# Current_AC.net
KiCad netlist of a schematic drawn in Altium Designer
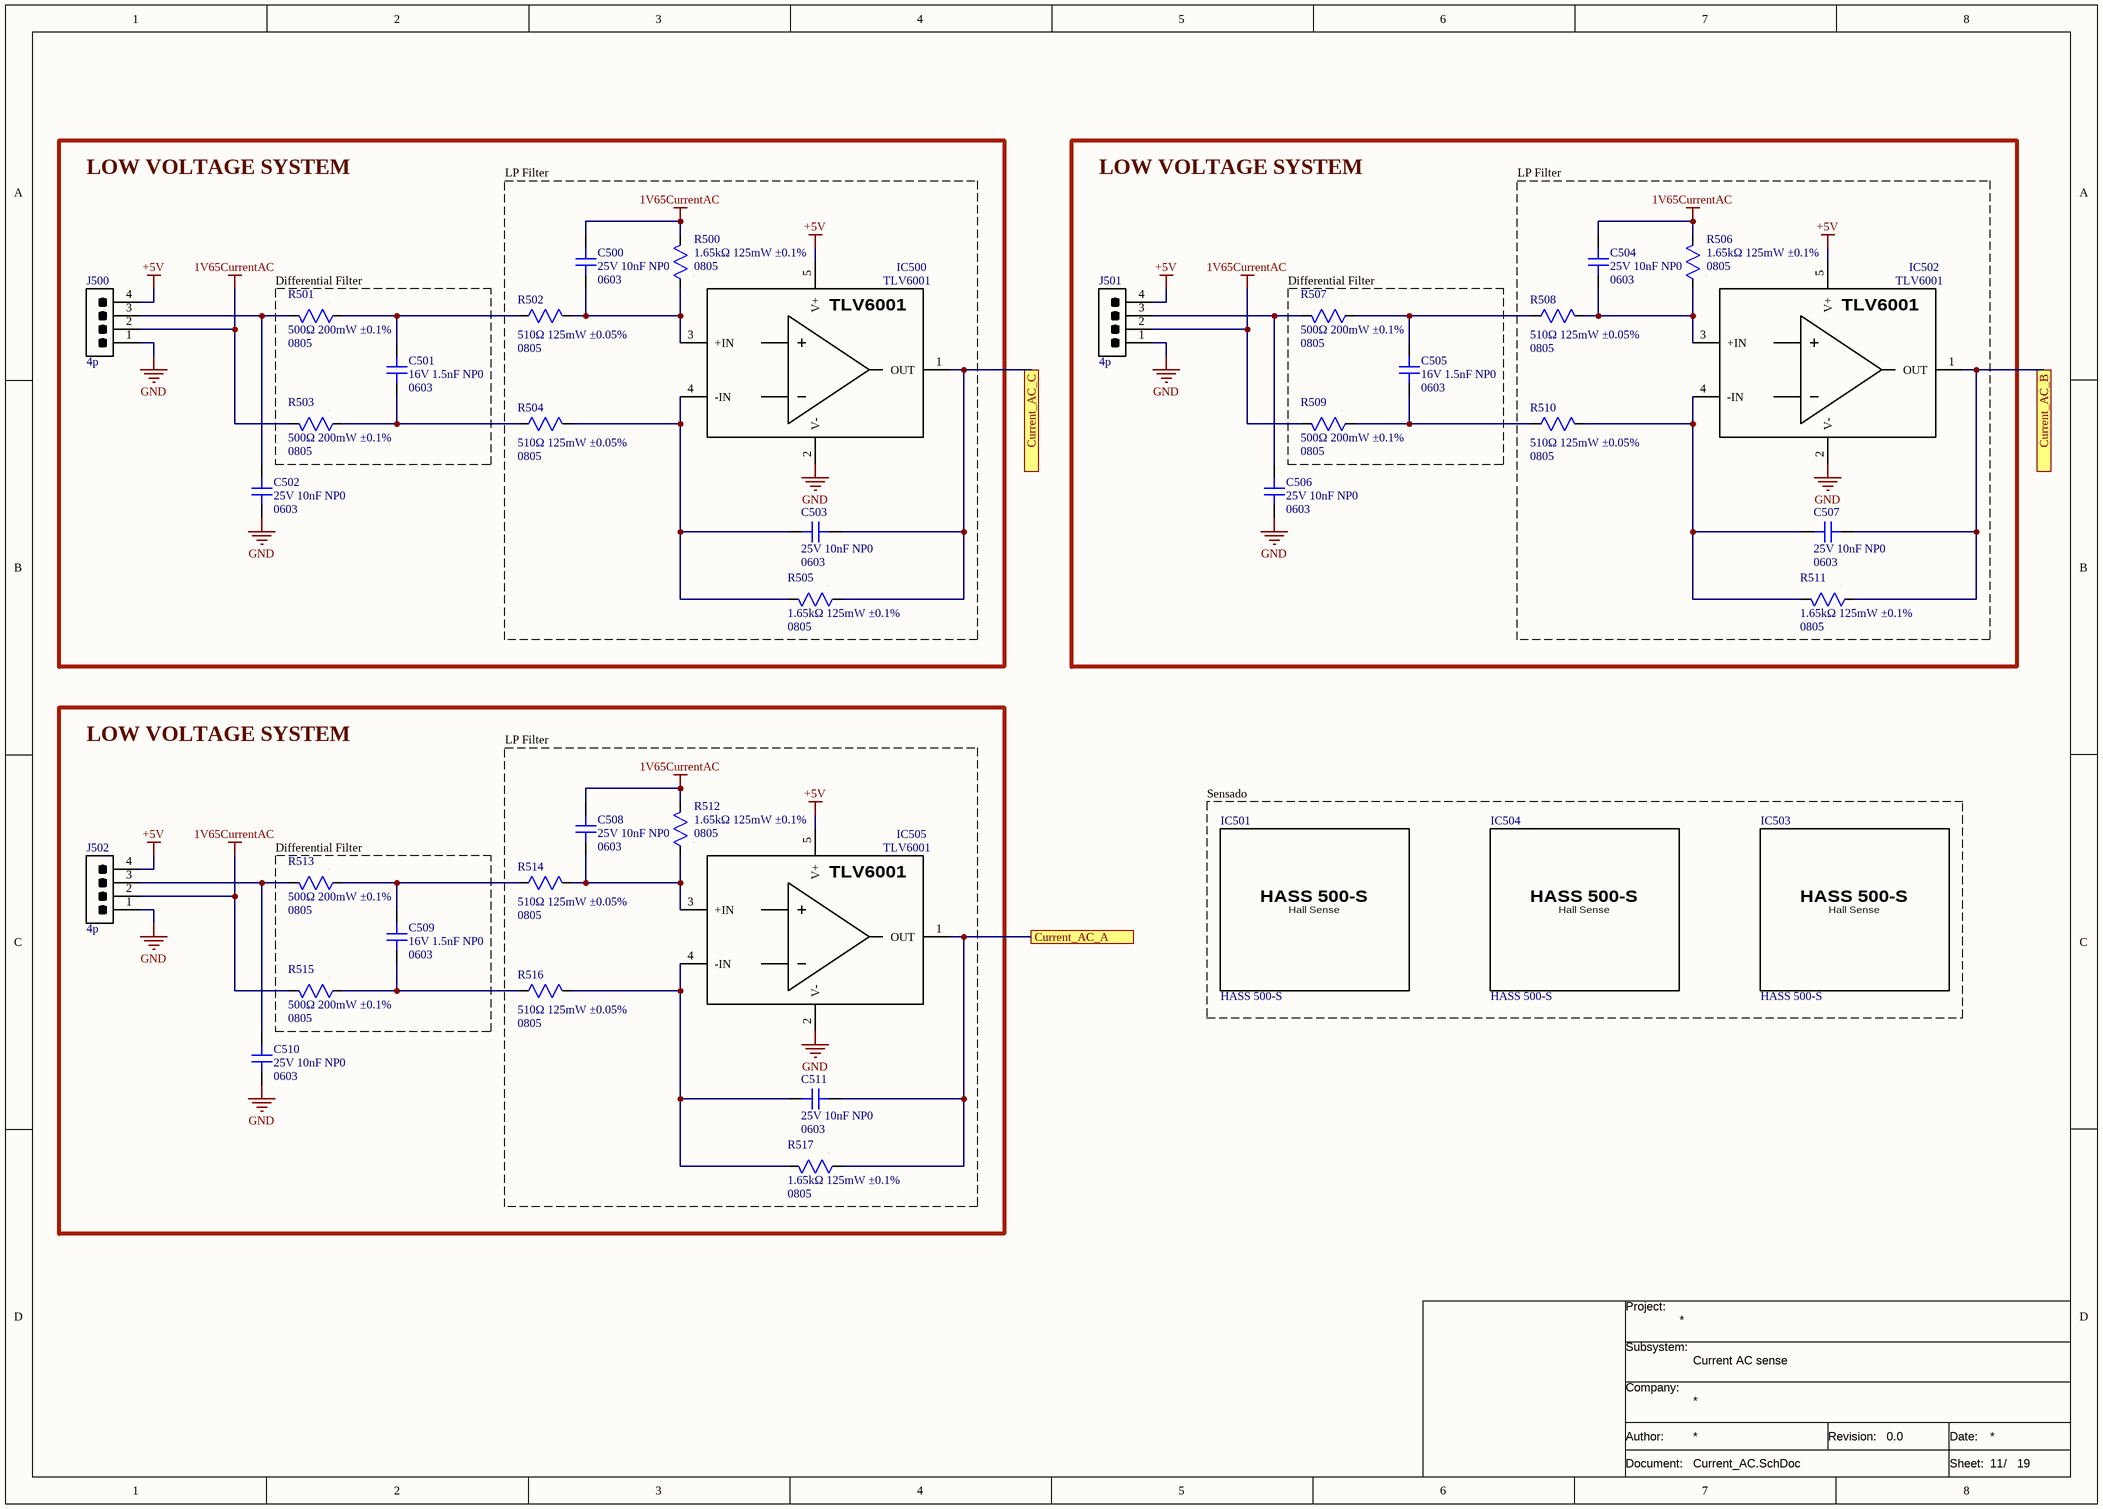
[diagram p0: Current_AC.SchDoc]

(export (version "E")
  (design (tool "Eeschema 10.0.6"))
  (components
    (comp (ref "C500")
      (value "25V 10nF NP0")
      (footprint "CAP SMD 0603")
      (description "Condensadores de cerámica multicapa (MLCC- SMD/SMT) 0.01 uF 25 VDC 1% 0603 C0G (NP0) AEC-Q200")
      (fields
        (field (name "PACKAGE") "0603")
        (field (name "MPN") "GRT1885C1E103FA02D")
        (field (name "MANUFACTURER") "muRata")
      )
      (libsource (lib "eUSR_Database") (part "CAP non polarized"))
    )
    (comp (ref "C501")
      (value "16V 1.5nF NP0")
      (footprint "CAP SMD 0603")
      (description "Condensadores de cerámica multicapa (MLCC- SMD/SMT) 25V 1500pF C0G 0603 1%")
      (fields
        (field (name "PACKAGE") "0603")
        (field (name "MPN") "C0603C152F3GECTU")
        (field (name "MANUFACTURER") "KEMET")
      )
      (libsource (lib "eUSR_Database") (part "CAP non polarized"))
    )
    (comp (ref "C502")
      (value "25V 10nF NP0")
      (footprint "CAP SMD 0603")
      (description "Condensadores de cerámica multicapa (MLCC- SMD/SMT) 0.01 uF 25 VDC 1% 0603 C0G (NP0) AEC-Q200")
      (fields
        (field (name "PACKAGE") "0603")
        (field (name "MPN") "GRT1885C1E103FA02D")
        (field (name "MANUFACTURER") "muRata")
      )
      (libsource (lib "eUSR_Database") (part "CAP non polarized"))
    )
    (comp (ref "C503")
      (value "25V 10nF NP0")
      (footprint "CAP SMD 0603")
      (description "Condensadores de cerámica multicapa (MLCC- SMD/SMT) 0.01 uF 25 VDC 1% 0603 C0G (NP0) AEC-Q200")
      (fields
        (field (name "PACKAGE") "0603")
        (field (name "MPN") "GRT1885C1E103FA02D")
        (field (name "MANUFACTURER") "muRata")
      )
      (libsource (lib "eUSR_Database") (part "CAP non polarized"))
    )
    (comp (ref "C504")
      (value "25V 10nF NP0")
      (footprint "CAP SMD 0603")
      (description "Condensadores de cerámica multicapa (MLCC- SMD/SMT) 0.01 uF 25 VDC 1% 0603 C0G (NP0) AEC-Q200")
      (fields
        (field (name "PACKAGE") "0603")
        (field (name "MPN") "GRT1885C1E103FA02D")
        (field (name "MANUFACTURER") "muRata")
      )
      (libsource (lib "eUSR_Database") (part "CAP non polarized"))
    )
    (comp (ref "C505")
      (value "16V 1.5nF NP0")
      (footprint "CAP SMD 0603")
      (description "Condensadores de cerámica multicapa (MLCC- SMD/SMT) 25V 1500pF C0G 0603 1%")
      (fields
        (field (name "PACKAGE") "0603")
        (field (name "MPN") "C0603C152F3GECTU")
        (field (name "MANUFACTURER") "KEMET")
      )
      (libsource (lib "eUSR_Database") (part "CAP non polarized"))
    )
    (comp (ref "C506")
      (value "25V 10nF NP0")
      (footprint "CAP SMD 0603")
      (description "Condensadores de cerámica multicapa (MLCC- SMD/SMT) 0.01 uF 25 VDC 1% 0603 C0G (NP0) AEC-Q200")
      (fields
        (field (name "PACKAGE") "0603")
        (field (name "MPN") "GRT1885C1E103FA02D")
        (field (name "MANUFACTURER") "muRata")
      )
      (libsource (lib "eUSR_Database") (part "CAP non polarized"))
    )
    (comp (ref "C507")
      (value "25V 10nF NP0")
      (footprint "CAP SMD 0603")
      (description "Condensadores de cerámica multicapa (MLCC- SMD/SMT) 0.01 uF 25 VDC 1% 0603 C0G (NP0) AEC-Q200")
      (fields
        (field (name "PACKAGE") "0603")
        (field (name "MPN") "GRT1885C1E103FA02D")
        (field (name "MANUFACTURER") "muRata")
      )
      (libsource (lib "eUSR_Database") (part "CAP non polarized"))
    )
    (comp (ref "C508")
      (value "25V 10nF NP0")
      (footprint "CAP SMD 0603")
      (description "Condensadores de cerámica multicapa (MLCC- SMD/SMT) 0.01 uF 25 VDC 1% 0603 C0G (NP0) AEC-Q200")
      (fields
        (field (name "PACKAGE") "0603")
        (field (name "MPN") "GRT1885C1E103FA02D")
        (field (name "MANUFACTURER") "muRata")
      )
      (libsource (lib "eUSR_Database") (part "CAP non polarized"))
    )
    (comp (ref "C509")
      (value "16V 1.5nF NP0")
      (footprint "CAP SMD 0603")
      (description "Condensadores de cerámica multicapa (MLCC- SMD/SMT) 25V 1500pF C0G 0603 1%")
      (fields
        (field (name "PACKAGE") "0603")
        (field (name "MPN") "C0603C152F3GECTU")
        (field (name "MANUFACTURER") "KEMET")
      )
      (libsource (lib "eUSR_Database") (part "CAP non polarized"))
    )
    (comp (ref "C510")
      (value "25V 10nF NP0")
      (footprint "CAP SMD 0603")
      (description "Condensadores de cerámica multicapa (MLCC- SMD/SMT) 0.01 uF 25 VDC 1% 0603 C0G (NP0) AEC-Q200")
      (fields
        (field (name "PACKAGE") "0603")
        (field (name "MPN") "GRT1885C1E103FA02D")
        (field (name "MANUFACTURER") "muRata")
      )
      (libsource (lib "eUSR_Database") (part "CAP non polarized"))
    )
    (comp (ref "C511")
      (value "25V 10nF NP0")
      (footprint "CAP SMD 0603")
      (description "Condensadores de cerámica multicapa (MLCC- SMD/SMT) 0.01 uF 25 VDC 1% 0603 C0G (NP0) AEC-Q200")
      (fields
        (field (name "PACKAGE") "0603")
        (field (name "MPN") "GRT1885C1E103FA02D")
        (field (name "MANUFACTURER") "muRata")
      )
      (libsource (lib "eUSR_Database") (part "CAP non polarized"))
    )
    (comp (ref "IC500")
      (value "TLV6001")
      (footprint "SOT-23-5")
      (fields (field (name "MPN") "TLV6001UIDBVR") (field (name "MANUFACTURER") "Texas Instruments"))
      (libsource (lib "eUSR_Database") (part "TLV6001"))
    )
    (comp (ref "IC501")
      (value "HASS 500-S")
      (footprint "HASS 500-S")
      (description "Sensores de corriente montados en placa")
      (fields (field (name "MANUFACTURER") "LEM"))
      (libsource (lib "eUSR_Database") (part "HASS 500-S"))
    )
    (comp (ref "IC502")
      (value "TLV6001")
      (footprint "SOT-23-5")
      (fields (field (name "MPN") "TLV6001UIDBVR") (field (name "MANUFACTURER") "Texas Instruments"))
      (libsource (lib "eUSR_Database") (part "TLV6001"))
    )
    (comp (ref "IC503")
      (value "HASS 500-S")
      (footprint "HASS 500-S")
      (description "Sensores de corriente montados en placa")
      (fields (field (name "MANUFACTURER") "LEM"))
      (libsource (lib "eUSR_Database") (part "HASS 500-S"))
    )
    (comp (ref "IC504")
      (value "HASS 500-S")
      (footprint "HASS 500-S")
      (description "Sensores de corriente montados en placa")
      (fields (field (name "MANUFACTURER") "LEM"))
      (libsource (lib "eUSR_Database") (part "HASS 500-S"))
    )
    (comp (ref "IC505")
      (value "TLV6001")
      (footprint "SOT-23-5")
      (fields (field (name "MPN") "TLV6001UIDBVR") (field (name "MANUFACTURER") "Texas Instruments"))
      (libsource (lib "eUSR_Database") (part "TLV6001"))
    )
    (comp (ref "J500")
      (value "4p")
      (footprint "B4B-XH-A-BK(LF)(SN)")
      (description "Alojamientos de cables y cabecera XH HEADER (TOP)")
      (fields (field (name "MPN") "B4B-XH-A-BK(LF)(SN)") (field (name "MANUFACTURER") "JST"))
      (libsource (lib "eUSR_Database") (part "CONN 4P"))
    )
    (comp (ref "J501")
      (value "4p")
      (footprint "B4B-XH-A-BK(LF)(SN)")
      (description "Alojamientos de cables y cabecera XH HEADER (TOP)")
      (fields (field (name "MPN") "B4B-XH-A-BK(LF)(SN)") (field (name "MANUFACTURER") "JST"))
      (libsource (lib "eUSR_Database") (part "CONN 4P"))
    )
    (comp (ref "J502")
      (value "4p")
      (footprint "B4B-XH-A-BK(LF)(SN)")
      (description "Alojamientos de cables y cabecera XH HEADER (TOP)")
      (fields (field (name "MPN") "B4B-XH-A-BK(LF)(SN)") (field (name "MANUFACTURER") "JST"))
      (libsource (lib "eUSR_Database") (part "CONN 4P"))
    )
    (comp (ref "R500")
      (value "1.65kΩ 125mW ±0.1%")
      (footprint "RES SMD 0805")
      (description "Thin Film Resistors MCU 0805-15 0.1% P1 1K65")
      (fields
        (field (name "PACKAGE") "0805")
        (field (name "MPN") "MCU08050E1651BP100")
        (field (name "MANUFACTURER") "Vishay")
      )
      (libsource (lib "eUSR_Database") (part "RES"))
    )
    (comp (ref "R501")
      (value "500Ω 200mW ±0.1%")
      (footprint "RES SMD 0805")
      (description "Resistores de película fina - SMD 0.2W 500ohm 0.1% 10ppm")
      (fields
        (field (name "PACKAGE") "0805")
        (field (name "MPN") "PTN0805Y5000BST1")
        (field (name "MANUFACTURER") "Vishay")
      )
      (libsource (lib "eUSR_Database") (part "RES"))
    )
    (comp (ref "R502")
      (value "510Ω 125mW ±0.05%")
      (footprint "RES SMD 0805")
      (description "Resistores de película fina - SMD 1/8W 510 Ohms 0.05% 0805 10ppm")
      (fields
        (field (name "PACKAGE") "0805")
        (field (name "MPN") "RG2012N-511-W-T1")
        (field (name "MANUFACTURER") "Susumu")
      )
      (libsource (lib "eUSR_Database") (part "RES"))
    )
    (comp (ref "R503")
      (value "500Ω 200mW ±0.1%")
      (footprint "RES SMD 0805")
      (description "Resistores de película fina - SMD 0.2W 500ohm 0.1% 10ppm")
      (fields
        (field (name "PACKAGE") "0805")
        (field (name "MPN") "PTN0805Y5000BST1")
        (field (name "MANUFACTURER") "Vishay")
      )
      (libsource (lib "eUSR_Database") (part "RES"))
    )
    (comp (ref "R504")
      (value "510Ω 125mW ±0.05%")
      (footprint "RES SMD 0805")
      (description "Resistores de película fina - SMD 1/8W 510 Ohms 0.05% 0805 10ppm")
      (fields
        (field (name "PACKAGE") "0805")
        (field (name "MPN") "RG2012N-511-W-T1")
        (field (name "MANUFACTURER") "Susumu")
      )
      (libsource (lib "eUSR_Database") (part "RES"))
    )
    (comp (ref "R505")
      (value "1.65kΩ 125mW ±0.1%")
      (footprint "RES SMD 0805")
      (description "Thin Film Resistors MCU 0805-15 0.1% P1 1K65")
      (fields
        (field (name "PACKAGE") "0805")
        (field (name "MPN") "MCU08050E1651BP100")
        (field (name "MANUFACTURER") "Vishay")
      )
      (libsource (lib "eUSR_Database") (part "RES"))
    )
    (comp (ref "R506")
      (value "1.65kΩ 125mW ±0.1%")
      (footprint "RES SMD 0805")
      (description "Thin Film Resistors MCU 0805-15 0.1% P1 1K65")
      (fields
        (field (name "PACKAGE") "0805")
        (field (name "MPN") "MCU08050E1651BP100")
        (field (name "MANUFACTURER") "Vishay")
      )
      (libsource (lib "eUSR_Database") (part "RES"))
    )
    (comp (ref "R507")
      (value "500Ω 200mW ±0.1%")
      (footprint "RES SMD 0805")
      (description "Resistores de película fina - SMD 0.2W 500ohm 0.1% 10ppm")
      (fields
        (field (name "PACKAGE") "0805")
        (field (name "MPN") "PTN0805Y5000BST1")
        (field (name "MANUFACTURER") "Vishay")
      )
      (libsource (lib "eUSR_Database") (part "RES"))
    )
    (comp (ref "R508")
      (value "510Ω 125mW ±0.05%")
      (footprint "RES SMD 0805")
      (description "Resistores de película fina - SMD 1/8W 510 Ohms 0.05% 0805 10ppm")
      (fields
        (field (name "PACKAGE") "0805")
        (field (name "MPN") "RG2012N-511-W-T1")
        (field (name "MANUFACTURER") "Susumu")
      )
      (libsource (lib "eUSR_Database") (part "RES"))
    )
    (comp (ref "R509")
      (value "500Ω 200mW ±0.1%")
      (footprint "RES SMD 0805")
      (description "Resistores de película fina - SMD 0.2W 500ohm 0.1% 10ppm")
      (fields
        (field (name "PACKAGE") "0805")
        (field (name "MPN") "PTN0805Y5000BST1")
        (field (name "MANUFACTURER") "Vishay")
      )
      (libsource (lib "eUSR_Database") (part "RES"))
    )
    (comp (ref "R510")
      (value "510Ω 125mW ±0.05%")
      (footprint "RES SMD 0805")
      (description "Resistores de película fina - SMD 1/8W 510 Ohms 0.05% 0805 10ppm")
      (fields
        (field (name "PACKAGE") "0805")
        (field (name "MPN") "RG2012N-511-W-T1")
        (field (name "MANUFACTURER") "Susumu")
      )
      (libsource (lib "eUSR_Database") (part "RES"))
    )
    (comp (ref "R511")
      (value "1.65kΩ 125mW ±0.1%")
      (footprint "RES SMD 0805")
      (description "Thin Film Resistors MCU 0805-15 0.1% P1 1K65")
      (fields
        (field (name "PACKAGE") "0805")
        (field (name "MPN") "MCU08050E1651BP100")
        (field (name "MANUFACTURER") "Vishay")
      )
      (libsource (lib "eUSR_Database") (part "RES"))
    )
    (comp (ref "R512")
      (value "1.65kΩ 125mW ±0.1%")
      (footprint "RES SMD 0805")
      (description "Thin Film Resistors MCU 0805-15 0.1% P1 1K65")
      (fields
        (field (name "PACKAGE") "0805")
        (field (name "MPN") "MCU08050E1651BP100")
        (field (name "MANUFACTURER") "Vishay")
      )
      (libsource (lib "eUSR_Database") (part "RES"))
    )
    (comp (ref "R513")
      (value "500Ω 200mW ±0.1%")
      (footprint "RES SMD 0805")
      (description "Resistores de película fina - SMD 0.2W 500ohm 0.1% 10ppm")
      (fields
        (field (name "PACKAGE") "0805")
        (field (name "MPN") "PTN0805Y5000BST1")
        (field (name "MANUFACTURER") "Vishay")
      )
      (libsource (lib "eUSR_Database") (part "RES"))
    )
    (comp (ref "R514")
      (value "510Ω 125mW ±0.05%")
      (footprint "RES SMD 0805")
      (description "Resistores de película fina - SMD 1/8W 510 Ohms 0.05% 0805 10ppm")
      (fields
        (field (name "PACKAGE") "0805")
        (field (name "MPN") "RG2012N-511-W-T1")
        (field (name "MANUFACTURER") "Susumu")
      )
      (libsource (lib "eUSR_Database") (part "RES"))
    )
    (comp (ref "R515")
      (value "500Ω 200mW ±0.1%")
      (footprint "RES SMD 0805")
      (description "Resistores de película fina - SMD 0.2W 500ohm 0.1% 10ppm")
      (fields
        (field (name "PACKAGE") "0805")
        (field (name "MPN") "PTN0805Y5000BST1")
        (field (name "MANUFACTURER") "Vishay")
      )
      (libsource (lib "eUSR_Database") (part "RES"))
    )
    (comp (ref "R516")
      (value "510Ω 125mW ±0.05%")
      (footprint "RES SMD 0805")
      (description "Resistores de película fina - SMD 1/8W 510 Ohms 0.05% 0805 10ppm")
      (fields
        (field (name "PACKAGE") "0805")
        (field (name "MPN") "RG2012N-511-W-T1")
        (field (name "MANUFACTURER") "Susumu")
      )
      (libsource (lib "eUSR_Database") (part "RES"))
    )
    (comp (ref "R517")
      (value "1.65kΩ 125mW ±0.1%")
      (footprint "RES SMD 0805")
      (description "Thin Film Resistors MCU 0805-15 0.1% P1 1K65")
      (fields
        (field (name "PACKAGE") "0805")
        (field (name "MPN") "MCU08050E1651BP100")
        (field (name "MANUFACTURER") "Vishay")
      )
      (libsource (lib "eUSR_Database") (part "RES"))
    )
  )
  (nets
    (net (code "1") (name "+5V") (class "Default")
      (node (ref "IC500") (pin "5") (pinfunction "V+_5") (pintype "passive"))
      (node (ref "IC502") (pin "5") (pinfunction "V+_5") (pintype "passive"))
      (node (ref "IC505") (pin "5") (pinfunction "V+_5") (pintype "passive"))
      (node (ref "J500") (pin "4") (pinfunction "4_4") (pintype "passive"))
      (node (ref "J501") (pin "4") (pinfunction "4_4") (pintype "passive"))
      (node (ref "J502") (pin "4") (pinfunction "4_4") (pintype "passive"))
    )
    (net (code "2") (name "/Current_AC_A") (class "Default")
      (node (ref "C511") (pin "2") (pinfunction "2_2") (pintype "passive"))
      (node (ref "IC505") (pin "1") (pinfunction "OUT_1") (pintype "passive"))
      (node (ref "R517") (pin "1") (pinfunction "1_1") (pintype "passive"))
    )
    (net (code "3") (name "/Current_AC_B") (class "Default")
      (node (ref "C507") (pin "2") (pinfunction "2_2") (pintype "passive"))
      (node (ref "IC502") (pin "1") (pinfunction "OUT_1") (pintype "passive"))
      (node (ref "R511") (pin "1") (pinfunction "1_1") (pintype "passive"))
    )
    (net (code "4") (name "/Current_AC_C") (class "Default")
      (node (ref "C503") (pin "2") (pinfunction "2_2") (pintype "passive"))
      (node (ref "IC500") (pin "1") (pinfunction "OUT_1") (pintype "passive"))
      (node (ref "R505") (pin "1") (pinfunction "1_1") (pintype "passive"))
    )
    (net (code "5") (name "1V65CurrentAC") (class "Default")
      (node (ref "C500") (pin "1") (pinfunction "1_1") (pintype "passive"))
      (node (ref "C504") (pin "1") (pinfunction "1_1") (pintype "passive"))
      (node (ref "C508") (pin "1") (pinfunction "1_1") (pintype "passive"))
      (node (ref "J500") (pin "2") (pinfunction "2_2") (pintype "passive"))
      (node (ref "J501") (pin "2") (pinfunction "2_2") (pintype "passive"))
      (node (ref "J502") (pin "2") (pinfunction "2_2") (pintype "passive"))
      (node (ref "R500") (pin "2") (pinfunction "2_2") (pintype "passive"))
      (node (ref "R503") (pin "2") (pinfunction "2_2") (pintype "passive"))
      (node (ref "R506") (pin "2") (pinfunction "2_2") (pintype "passive"))
      (node (ref "R509") (pin "2") (pinfunction "2_2") (pintype "passive"))
      (node (ref "R512") (pin "2") (pinfunction "2_2") (pintype "passive"))
      (node (ref "R515") (pin "2") (pinfunction "2_2") (pintype "passive"))
    )
    (net (code "6") (name "GND") (class "Default")
      (node (ref "C502") (pin "2") (pinfunction "2_2") (pintype "passive"))
      (node (ref "C506") (pin "2") (pinfunction "2_2") (pintype "passive"))
      (node (ref "C510") (pin "2") (pinfunction "2_2") (pintype "passive"))
      (node (ref "IC500") (pin "2") (pinfunction "V-_2") (pintype "passive"))
      (node (ref "IC502") (pin "2") (pinfunction "V-_2") (pintype "passive"))
      (node (ref "IC505") (pin "2") (pinfunction "V-_2") (pintype "passive"))
      (node (ref "J500") (pin "1") (pinfunction "1_1") (pintype "passive"))
      (node (ref "J501") (pin "1") (pinfunction "1_1") (pintype "passive"))
      (node (ref "J502") (pin "1") (pinfunction "1_1") (pintype "passive"))
    )
    (net (code "7") (name "Net-(C501-Pad1)") (class "Default")
      (node (ref "C501") (pin "1") (pinfunction "1_1") (pintype "passive"))
      (node (ref "R501") (pin "1") (pinfunction "1_1") (pintype "passive"))
      (node (ref "R502") (pin "1") (pinfunction "1_1") (pintype "passive"))
    )
    (net (code "8") (name "Net-(C501-Pad2)") (class "Default")
      (node (ref "C501") (pin "2") (pinfunction "2_2") (pintype "passive"))
      (node (ref "R503") (pin "1") (pinfunction "1_1") (pintype "passive"))
      (node (ref "R504") (pin "1") (pinfunction "1_1") (pintype "passive"))
    )
    (net (code "9") (name "Net-(C502-Pad1)") (class "Default")
      (node (ref "C502") (pin "1") (pinfunction "1_1") (pintype "passive"))
      (node (ref "J500") (pin "3") (pinfunction "3_3") (pintype "passive"))
      (node (ref "R501") (pin "2") (pinfunction "2_2") (pintype "passive"))
    )
    (net (code "10") (name "Net-(C505-Pad1)") (class "Default")
      (node (ref "C505") (pin "1") (pinfunction "1_1") (pintype "passive"))
      (node (ref "R507") (pin "1") (pinfunction "1_1") (pintype "passive"))
      (node (ref "R508") (pin "1") (pinfunction "1_1") (pintype "passive"))
    )
    (net (code "11") (name "Net-(C505-Pad2)") (class "Default")
      (node (ref "C505") (pin "2") (pinfunction "2_2") (pintype "passive"))
      (node (ref "R509") (pin "1") (pinfunction "1_1") (pintype "passive"))
      (node (ref "R510") (pin "1") (pinfunction "1_1") (pintype "passive"))
    )
    (net (code "12") (name "Net-(C506-Pad1)") (class "Default")
      (node (ref "C506") (pin "1") (pinfunction "1_1") (pintype "passive"))
      (node (ref "J501") (pin "3") (pinfunction "3_3") (pintype "passive"))
      (node (ref "R507") (pin "2") (pinfunction "2_2") (pintype "passive"))
    )
    (net (code "13") (name "Net-(C509-Pad1)") (class "Default")
      (node (ref "C509") (pin "1") (pinfunction "1_1") (pintype "passive"))
      (node (ref "R513") (pin "1") (pinfunction "1_1") (pintype "passive"))
      (node (ref "R514") (pin "1") (pinfunction "1_1") (pintype "passive"))
    )
    (net (code "14") (name "Net-(C509-Pad2)") (class "Default")
      (node (ref "C509") (pin "2") (pinfunction "2_2") (pintype "passive"))
      (node (ref "R515") (pin "1") (pinfunction "1_1") (pintype "passive"))
      (node (ref "R516") (pin "1") (pinfunction "1_1") (pintype "passive"))
    )
    (net (code "15") (name "Net-(C510-Pad1)") (class "Default")
      (node (ref "C510") (pin "1") (pinfunction "1_1") (pintype "passive"))
      (node (ref "J502") (pin "3") (pinfunction "3_3") (pintype "passive"))
      (node (ref "R513") (pin "2") (pinfunction "2_2") (pintype "passive"))
    )
    (net (code "16") (name "Net-(IC500-+IN)") (class "Default")
      (node (ref "C500") (pin "2") (pinfunction "2_2") (pintype "passive"))
      (node (ref "IC500") (pin "3") (pinfunction "+IN_3") (pintype "passive"))
      (node (ref "R500") (pin "1") (pinfunction "1_1") (pintype "passive"))
      (node (ref "R502") (pin "2") (pinfunction "2_2") (pintype "passive"))
    )
    (net (code "17") (name "Net-(IC500--IN)") (class "Default")
      (node (ref "C503") (pin "1") (pinfunction "1_1") (pintype "passive"))
      (node (ref "IC500") (pin "4") (pinfunction "-IN_4") (pintype "passive"))
      (node (ref "R504") (pin "2") (pinfunction "2_2") (pintype "passive"))
      (node (ref "R505") (pin "2") (pinfunction "2_2") (pintype "passive"))
    )
    (net (code "18") (name "Net-(IC502-+IN)") (class "Default")
      (node (ref "C504") (pin "2") (pinfunction "2_2") (pintype "passive"))
      (node (ref "IC502") (pin "3") (pinfunction "+IN_3") (pintype "passive"))
      (node (ref "R506") (pin "1") (pinfunction "1_1") (pintype "passive"))
      (node (ref "R508") (pin "2") (pinfunction "2_2") (pintype "passive"))
    )
    (net (code "19") (name "Net-(IC502--IN)") (class "Default")
      (node (ref "C507") (pin "1") (pinfunction "1_1") (pintype "passive"))
      (node (ref "IC502") (pin "4") (pinfunction "-IN_4") (pintype "passive"))
      (node (ref "R510") (pin "2") (pinfunction "2_2") (pintype "passive"))
      (node (ref "R511") (pin "2") (pinfunction "2_2") (pintype "passive"))
    )
    (net (code "20") (name "Net-(IC505-+IN)") (class "Default")
      (node (ref "C508") (pin "2") (pinfunction "2_2") (pintype "passive"))
      (node (ref "IC505") (pin "3") (pinfunction "+IN_3") (pintype "passive"))
      (node (ref "R512") (pin "1") (pinfunction "1_1") (pintype "passive"))
      (node (ref "R514") (pin "2") (pinfunction "2_2") (pintype "passive"))
    )
    (net (code "21") (name "Net-(IC505--IN)") (class "Default")
      (node (ref "C511") (pin "1") (pinfunction "1_1") (pintype "passive"))
      (node (ref "IC505") (pin "4") (pinfunction "-IN_4") (pintype "passive"))
      (node (ref "R516") (pin "2") (pinfunction "2_2") (pintype "passive"))
      (node (ref "R517") (pin "2") (pinfunction "2_2") (pintype "passive"))
    )
  )
)
